# BBBExtend.net
KiCad netlist of a schematic drawn in Altium Designer
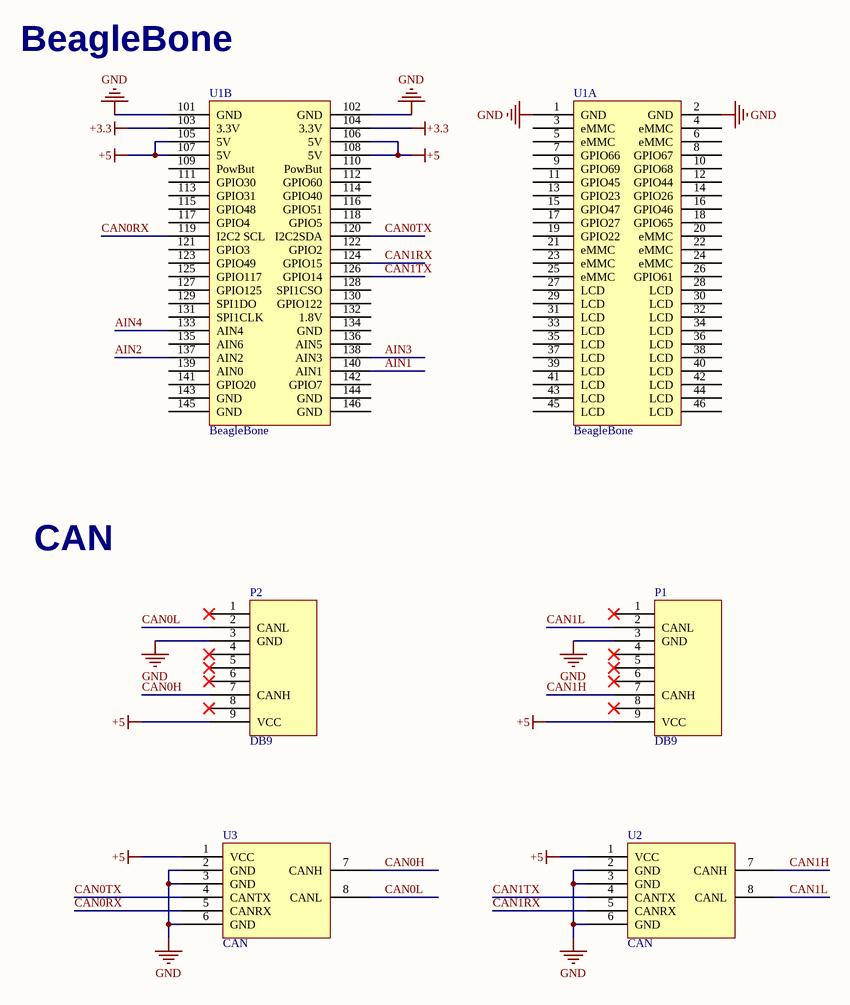
[diagram p0: BBBExtend.SchDoc]

(export (version "E")
  (design (tool "Eeschema 10.0.6"))
  (components
    (comp (ref "P1") (value "DB9") (footprint "DB9") (libsource (lib "Schlib1") (part "DB9")))
    (comp (ref "P2") (value "DB9") (footprint "DB9") (libsource (lib "Schlib1") (part "DB9")))
    (comp (ref "U1")
      (value "BeagleBone")
      (footprint "BeagleBoneB")
      (libsource (lib "Schlib1") (part "BeagleBone"))
    )
    (comp (ref "U2") (value "CAN") (footprint "CANTRer") (libsource (lib "Schlib1") (part "CAN")))
    (comp (ref "U3") (value "CAN") (footprint "CANTRer") (libsource (lib "Schlib1") (part "CAN")))
  )
  (nets
    (net (code "1") (name "+3.3") (class "Default")
      (node (ref "U1") (pin "103") (pinfunction "3.3V_103") (pintype "passive"))
      (node (ref "U1") (pin "104") (pinfunction "3.3V_104") (pintype "passive"))
    )
    (net (code "2") (name "+5") (class "Default")
      (node (ref "P1") (pin "9") (pinfunction "VCC_9") (pintype "passive"))
      (node (ref "P2") (pin "9") (pinfunction "VCC_9") (pintype "passive"))
      (node (ref "U1") (pin "105") (pinfunction "5V_105") (pintype "passive"))
      (node (ref "U1") (pin "106") (pinfunction "5V_106") (pintype "passive"))
      (node (ref "U1") (pin "107") (pinfunction "5V_107") (pintype "passive"))
      (node (ref "U1") (pin "108") (pinfunction "5V_108") (pintype "passive"))
      (node (ref "U2") (pin "1") (pinfunction "VCC_1") (pintype "passive"))
      (node (ref "U3") (pin "1") (pinfunction "VCC_1") (pintype "passive"))
    )
    (net (code "3") (name "/AIN1") (class "Default")
      (node (ref "U1") (pin "140") (pinfunction "AIN1_140") (pintype "passive"))
    )
    (net (code "4") (name "/AIN2") (class "Default")
      (node (ref "U1") (pin "137") (pinfunction "AIN2_137") (pintype "passive"))
    )
    (net (code "5") (name "/AIN3") (class "Default")
      (node (ref "U1") (pin "138") (pinfunction "AIN3_138") (pintype "passive"))
    )
    (net (code "6") (name "/AIN4") (class "Default")
      (node (ref "U1") (pin "133") (pinfunction "AIN4_133") (pintype "passive"))
    )
    (net (code "7") (name "/CAN0H") (class "Default")
      (node (ref "P2") (pin "7") (pinfunction "CANH_7") (pintype "passive"))
      (node (ref "U3") (pin "7") (pinfunction "CANH_7") (pintype "passive"))
    )
    (net (code "8") (name "/CAN0L") (class "Default")
      (node (ref "P2") (pin "2") (pinfunction "CANL_2") (pintype "passive"))
      (node (ref "U3") (pin "8") (pinfunction "CANL_8") (pintype "passive"))
    )
    (net (code "9") (name "/CAN0RX") (class "Default")
      (node (ref "U1") (pin "119") (pinfunction "I2C2_SCL_119") (pintype "passive"))
      (node (ref "U3") (pin "5") (pinfunction "CANRX_5") (pintype "passive"))
    )
    (net (code "10") (name "/CAN0TX") (class "Default")
      (node (ref "U1") (pin "120") (pinfunction "I2C2SDA_120") (pintype "passive"))
      (node (ref "U3") (pin "4") (pinfunction "CANTX_4") (pintype "passive"))
    )
    (net (code "11") (name "/CAN1H") (class "Default")
      (node (ref "P1") (pin "7") (pinfunction "CANH_7") (pintype "passive"))
      (node (ref "U2") (pin "7") (pinfunction "CANH_7") (pintype "passive"))
    )
    (net (code "12") (name "/CAN1L") (class "Default")
      (node (ref "P1") (pin "2") (pinfunction "CANL_2") (pintype "passive"))
      (node (ref "U2") (pin "8") (pinfunction "CANL_8") (pintype "passive"))
    )
    (net (code "13") (name "/CAN1RX") (class "Default")
      (node (ref "U1") (pin "124") (pinfunction "GPIO15_124") (pintype "passive"))
      (node (ref "U2") (pin "5") (pinfunction "CANRX_5") (pintype "passive"))
    )
    (net (code "14") (name "/CAN1TX") (class "Default")
      (node (ref "U1") (pin "126") (pinfunction "GPIO14_126") (pintype "passive"))
      (node (ref "U2") (pin "4") (pinfunction "CANTX_4") (pintype "passive"))
    )
    (net (code "15") (name "GND") (class "Default")
      (node (ref "P1") (pin "3") (pinfunction "GND_3") (pintype "passive"))
      (node (ref "P2") (pin "3") (pinfunction "GND_3") (pintype "passive"))
      (node (ref "U1") (pin "1") (pinfunction "GND_1") (pintype "passive"))
      (node (ref "U1") (pin "101") (pinfunction "GND_101") (pintype "passive"))
      (node (ref "U1") (pin "102") (pinfunction "GND_102") (pintype "passive"))
      (node (ref "U1") (pin "2") (pinfunction "GND_2") (pintype "passive"))
      (node (ref "U2") (pin "2") (pinfunction "GND_2") (pintype "passive"))
      (node (ref "U2") (pin "3") (pinfunction "GND_3") (pintype "passive"))
      (node (ref "U2") (pin "6") (pinfunction "GND_6") (pintype "passive"))
      (node (ref "U3") (pin "2") (pinfunction "GND_2") (pintype "passive"))
      (node (ref "U3") (pin "3") (pinfunction "GND_3") (pintype "passive"))
      (node (ref "U3") (pin "6") (pinfunction "GND_6") (pintype "passive"))
    )
    (net (code "16") (name "unconnected-(P1-Pad1)") (class "Default")
      (node (ref "P1") (pin "1") (pintype "passive+no_connect"))
    )
    (net (code "17") (name "unconnected-(P1-Pad4)") (class "Default")
      (node (ref "P1") (pin "4") (pintype "passive+no_connect"))
    )
    (net (code "18") (name "unconnected-(P1-Pad5)") (class "Default")
      (node (ref "P1") (pin "5") (pintype "passive+no_connect"))
    )
    (net (code "19") (name "unconnected-(P1-Pad6)") (class "Default")
      (node (ref "P1") (pin "6") (pintype "passive+no_connect"))
    )
    (net (code "20") (name "unconnected-(P1-Pad8)") (class "Default")
      (node (ref "P1") (pin "8") (pintype "passive+no_connect"))
    )
    (net (code "21") (name "unconnected-(P2-Pad1)") (class "Default")
      (node (ref "P2") (pin "1") (pintype "passive+no_connect"))
    )
    (net (code "22") (name "unconnected-(P2-Pad4)") (class "Default")
      (node (ref "P2") (pin "4") (pintype "passive+no_connect"))
    )
    (net (code "23") (name "unconnected-(P2-Pad5)") (class "Default")
      (node (ref "P2") (pin "5") (pintype "passive+no_connect"))
    )
    (net (code "24") (name "unconnected-(P2-Pad6)") (class "Default")
      (node (ref "P2") (pin "6") (pintype "passive+no_connect"))
    )
    (net (code "25") (name "unconnected-(P2-Pad8)") (class "Default")
      (node (ref "P2") (pin "8") (pintype "passive+no_connect"))
    )
    (net (code "26") (name "unconnected-(U1A-GPIO22-Pad19)") (class "Default")
      (node (ref "U1") (pin "19") (pinfunction "GPIO22_19") (pintype "passive"))
    )
    (net (code "27") (name "unconnected-(U1A-GPIO23-Pad13)") (class "Default")
      (node (ref "U1") (pin "13") (pinfunction "GPIO23_13") (pintype "passive"))
    )
    (net (code "28") (name "unconnected-(U1A-GPIO26-Pad14)") (class "Default")
      (node (ref "U1") (pin "14") (pinfunction "GPIO26_14") (pintype "passive"))
    )
    (net (code "29") (name "unconnected-(U1A-GPIO27-Pad17)") (class "Default")
      (node (ref "U1") (pin "17") (pinfunction "GPIO27_17") (pintype "passive"))
    )
    (net (code "30") (name "unconnected-(U1A-GPIO44-Pad12)") (class "Default")
      (node (ref "U1") (pin "12") (pinfunction "GPIO44_12") (pintype "passive"))
    )
    (net (code "31") (name "unconnected-(U1A-GPIO45-Pad11)") (class "Default")
      (node (ref "U1") (pin "11") (pinfunction "GPIO45_11") (pintype "passive"))
    )
    (net (code "32") (name "unconnected-(U1A-GPIO46-Pad16)") (class "Default")
      (node (ref "U1") (pin "16") (pinfunction "GPIO46_16") (pintype "passive"))
    )
    (net (code "33") (name "unconnected-(U1A-GPIO47-Pad15)") (class "Default")
      (node (ref "U1") (pin "15") (pinfunction "GPIO47_15") (pintype "passive"))
    )
    (net (code "34") (name "unconnected-(U1A-GPIO61-Pad26)") (class "Default")
      (node (ref "U1") (pin "26") (pinfunction "GPIO61_26") (pintype "passive"))
    )
    (net (code "35") (name "unconnected-(U1A-GPIO65-Pad18)") (class "Default")
      (node (ref "U1") (pin "18") (pinfunction "GPIO65_18") (pintype "passive"))
    )
    (net (code "36") (name "unconnected-(U1A-GPIO66-Pad7)") (class "Default")
      (node (ref "U1") (pin "7") (pinfunction "GPIO66_7") (pintype "passive"))
    )
    (net (code "37") (name "unconnected-(U1A-GPIO67-Pad8)") (class "Default")
      (node (ref "U1") (pin "8") (pinfunction "GPIO67_8") (pintype "passive"))
    )
    (net (code "38") (name "unconnected-(U1A-GPIO68-Pad10)") (class "Default")
      (node (ref "U1") (pin "10") (pinfunction "GPIO68_10") (pintype "passive"))
    )
    (net (code "39") (name "unconnected-(U1A-GPIO69-Pad9)") (class "Default")
      (node (ref "U1") (pin "9") (pinfunction "GPIO69_9") (pintype "passive"))
    )
    (net (code "40") (name "unconnected-(U1A-LCD-Pad27)") (class "Default")
      (node (ref "U1") (pin "27") (pinfunction "LCD_27") (pintype "passive"))
    )
    (net (code "41") (name "unconnected-(U1A-LCD-Pad28)") (class "Default")
      (node (ref "U1") (pin "28") (pinfunction "LCD_28") (pintype "passive"))
    )
    (net (code "42") (name "unconnected-(U1A-LCD-Pad29)") (class "Default")
      (node (ref "U1") (pin "29") (pinfunction "LCD_29") (pintype "passive"))
    )
    (net (code "43") (name "unconnected-(U1A-LCD-Pad30)") (class "Default")
      (node (ref "U1") (pin "30") (pinfunction "LCD_30") (pintype "passive"))
    )
    (net (code "44") (name "unconnected-(U1A-LCD-Pad31)") (class "Default")
      (node (ref "U1") (pin "31") (pinfunction "LCD_31") (pintype "passive"))
    )
    (net (code "45") (name "unconnected-(U1A-LCD-Pad32)") (class "Default")
      (node (ref "U1") (pin "32") (pinfunction "LCD_32") (pintype "passive"))
    )
    (net (code "46") (name "unconnected-(U1A-LCD-Pad33)") (class "Default")
      (node (ref "U1") (pin "33") (pinfunction "LCD_33") (pintype "passive"))
    )
    (net (code "47") (name "unconnected-(U1A-LCD-Pad34)") (class "Default")
      (node (ref "U1") (pin "34") (pinfunction "LCD_34") (pintype "passive"))
    )
    (net (code "48") (name "unconnected-(U1A-LCD-Pad35)") (class "Default")
      (node (ref "U1") (pin "35") (pinfunction "LCD_35") (pintype "passive"))
    )
    (net (code "49") (name "unconnected-(U1A-LCD-Pad36)") (class "Default")
      (node (ref "U1") (pin "36") (pinfunction "LCD_36") (pintype "passive"))
    )
    (net (code "50") (name "unconnected-(U1A-LCD-Pad37)") (class "Default")
      (node (ref "U1") (pin "37") (pinfunction "LCD_37") (pintype "passive"))
    )
    (net (code "51") (name "unconnected-(U1A-LCD-Pad38)") (class "Default")
      (node (ref "U1") (pin "38") (pinfunction "LCD_38") (pintype "passive"))
    )
    (net (code "52") (name "unconnected-(U1A-LCD-Pad39)") (class "Default")
      (node (ref "U1") (pin "39") (pinfunction "LCD_39") (pintype "passive"))
    )
    (net (code "53") (name "unconnected-(U1A-LCD-Pad40)") (class "Default")
      (node (ref "U1") (pin "40") (pinfunction "LCD_40") (pintype "passive"))
    )
    (net (code "54") (name "unconnected-(U1A-LCD-Pad41)") (class "Default")
      (node (ref "U1") (pin "41") (pinfunction "LCD_41") (pintype "passive"))
    )
    (net (code "55") (name "unconnected-(U1A-LCD-Pad42)") (class "Default")
      (node (ref "U1") (pin "42") (pinfunction "LCD_42") (pintype "passive"))
    )
    (net (code "56") (name "unconnected-(U1A-LCD-Pad43)") (class "Default")
      (node (ref "U1") (pin "43") (pinfunction "LCD_43") (pintype "passive"))
    )
    (net (code "57") (name "unconnected-(U1A-LCD-Pad44)") (class "Default")
      (node (ref "U1") (pin "44") (pinfunction "LCD_44") (pintype "passive"))
    )
    (net (code "58") (name "unconnected-(U1A-LCD-Pad45)") (class "Default")
      (node (ref "U1") (pin "45") (pinfunction "LCD_45") (pintype "passive"))
    )
    (net (code "59") (name "unconnected-(U1A-LCD-Pad46)") (class "Default")
      (node (ref "U1") (pin "46") (pinfunction "LCD_46") (pintype "passive"))
    )
    (net (code "60") (name "unconnected-(U1A-eMMC-Pad3)") (class "Default")
      (node (ref "U1") (pin "3") (pinfunction "eMMC_3") (pintype "passive"))
    )
    (net (code "61") (name "unconnected-(U1A-eMMC-Pad4)") (class "Default")
      (node (ref "U1") (pin "4") (pinfunction "eMMC_4") (pintype "passive"))
    )
    (net (code "62") (name "unconnected-(U1A-eMMC-Pad5)") (class "Default")
      (node (ref "U1") (pin "5") (pinfunction "eMMC_5") (pintype "passive"))
    )
    (net (code "63") (name "unconnected-(U1A-eMMC-Pad6)") (class "Default")
      (node (ref "U1") (pin "6") (pinfunction "eMMC_6") (pintype "passive"))
    )
    (net (code "64") (name "unconnected-(U1A-eMMC-Pad20)") (class "Default")
      (node (ref "U1") (pin "20") (pinfunction "eMMC_20") (pintype "passive"))
    )
    (net (code "65") (name "unconnected-(U1A-eMMC-Pad21)") (class "Default")
      (node (ref "U1") (pin "21") (pinfunction "eMMC_21") (pintype "passive"))
    )
    (net (code "66") (name "unconnected-(U1A-eMMC-Pad22)") (class "Default")
      (node (ref "U1") (pin "22") (pinfunction "eMMC_22") (pintype "passive"))
    )
    (net (code "67") (name "unconnected-(U1A-eMMC-Pad23)") (class "Default")
      (node (ref "U1") (pin "23") (pinfunction "eMMC_23") (pintype "passive"))
    )
    (net (code "68") (name "unconnected-(U1A-eMMC-Pad24)") (class "Default")
      (node (ref "U1") (pin "24") (pinfunction "eMMC_24") (pintype "passive"))
    )
    (net (code "69") (name "unconnected-(U1A-eMMC-Pad25)") (class "Default")
      (node (ref "U1") (pin "25") (pinfunction "eMMC_25") (pintype "passive"))
    )
    (net (code "70") (name "unconnected-(U1B-1.8V-Pad132)") (class "Default")
      (node (ref "U1") (pin "132") (pinfunction "1.8V_132") (pintype "passive"))
    )
    (net (code "71") (name "unconnected-(U1B-AIN0-Pad139)") (class "Default")
      (node (ref "U1") (pin "139") (pinfunction "AIN0_139") (pintype "passive"))
    )
    (net (code "72") (name "unconnected-(U1B-AIN5-Pad136)") (class "Default")
      (node (ref "U1") (pin "136") (pinfunction "AIN5_136") (pintype "passive"))
    )
    (net (code "73") (name "unconnected-(U1B-AIN6-Pad135)") (class "Default")
      (node (ref "U1") (pin "135") (pinfunction "AIN6_135") (pintype "passive"))
    )
    (net (code "74") (name "unconnected-(U1B-GND-Pad134)") (class "Default")
      (node (ref "U1") (pin "134") (pinfunction "GND_134") (pintype "passive"))
    )
    (net (code "75") (name "unconnected-(U1B-GND-Pad143)") (class "Default")
      (node (ref "U1") (pin "143") (pinfunction "GND_143") (pintype "passive"))
    )
    (net (code "76") (name "unconnected-(U1B-GND-Pad144)") (class "Default")
      (node (ref "U1") (pin "144") (pinfunction "GND_144") (pintype "passive"))
    )
    (net (code "77") (name "unconnected-(U1B-GND-Pad145)") (class "Default")
      (node (ref "U1") (pin "145") (pinfunction "GND_145") (pintype "passive"))
    )
    (net (code "78") (name "unconnected-(U1B-GND-Pad146)") (class "Default")
      (node (ref "U1") (pin "146") (pinfunction "GND_146") (pintype "passive"))
    )
    (net (code "79") (name "unconnected-(U1B-GPIO2-Pad122)") (class "Default")
      (node (ref "U1") (pin "122") (pinfunction "GPIO2_122") (pintype "passive"))
    )
    (net (code "80") (name "unconnected-(U1B-GPIO3-Pad121)") (class "Default")
      (node (ref "U1") (pin "121") (pinfunction "GPIO3_121") (pintype "passive"))
    )
    (net (code "81") (name "unconnected-(U1B-GPIO4-Pad117)") (class "Default")
      (node (ref "U1") (pin "117") (pinfunction "GPIO4_117") (pintype "passive"))
    )
    (net (code "82") (name "unconnected-(U1B-GPIO5-Pad118)") (class "Default")
      (node (ref "U1") (pin "118") (pinfunction "GPIO5_118") (pintype "passive"))
    )
    (net (code "83") (name "unconnected-(U1B-GPIO7-Pad142)") (class "Default")
      (node (ref "U1") (pin "142") (pinfunction "GPIO7_142") (pintype "passive"))
    )
    (net (code "84") (name "unconnected-(U1B-GPIO20-Pad141)") (class "Default")
      (node (ref "U1") (pin "141") (pinfunction "GPIO20_141") (pintype "passive"))
    )
    (net (code "85") (name "unconnected-(U1B-GPIO30-Pad111)") (class "Default")
      (node (ref "U1") (pin "111") (pinfunction "GPIO30_111") (pintype "passive"))
    )
    (net (code "86") (name "unconnected-(U1B-GPIO31-Pad113)") (class "Default")
      (node (ref "U1") (pin "113") (pinfunction "GPIO31_113") (pintype "passive"))
    )
    (net (code "87") (name "unconnected-(U1B-GPIO40-Pad114)") (class "Default")
      (node (ref "U1") (pin "114") (pinfunction "GPIO40_114") (pintype "passive"))
    )
    (net (code "88") (name "unconnected-(U1B-GPIO48-Pad115)") (class "Default")
      (node (ref "U1") (pin "115") (pinfunction "GPIO48_115") (pintype "passive"))
    )
    (net (code "89") (name "unconnected-(U1B-GPIO49-Pad123)") (class "Default")
      (node (ref "U1") (pin "123") (pinfunction "GPIO49_123") (pintype "passive"))
    )
    (net (code "90") (name "unconnected-(U1B-GPIO51-Pad116)") (class "Default")
      (node (ref "U1") (pin "116") (pinfunction "GPIO51_116") (pintype "passive"))
    )
    (net (code "91") (name "unconnected-(U1B-GPIO60-Pad112)") (class "Default")
      (node (ref "U1") (pin "112") (pinfunction "GPIO60_112") (pintype "passive"))
    )
    (net (code "92") (name "unconnected-(U1B-GPIO117-Pad125)") (class "Default")
      (node (ref "U1") (pin "125") (pinfunction "GPIO117_125") (pintype "passive"))
    )
    (net (code "93") (name "unconnected-(U1B-GPIO122-Pad130)") (class "Default")
      (node (ref "U1") (pin "130") (pinfunction "GPIO122_130") (pintype "passive"))
    )
    (net (code "94") (name "unconnected-(U1B-GPIO125-Pad127)") (class "Default")
      (node (ref "U1") (pin "127") (pinfunction "GPIO125_127") (pintype "passive"))
    )
    (net (code "95") (name "unconnected-(U1B-PowBut-Pad109)") (class "Default")
      (node (ref "U1") (pin "109") (pinfunction "PowBut_109") (pintype "passive"))
    )
    (net (code "96") (name "unconnected-(U1B-PowBut-Pad110)") (class "Default")
      (node (ref "U1") (pin "110") (pinfunction "PowBut_110") (pintype "passive"))
    )
    (net (code "97") (name "unconnected-(U1B-SPI1CLK-Pad131)") (class "Default")
      (node (ref "U1") (pin "131") (pinfunction "SPI1CLK_131") (pintype "passive"))
    )
    (net (code "98") (name "unconnected-(U1B-SPI1CSO-Pad128)") (class "Default")
      (node (ref "U1") (pin "128") (pinfunction "SPI1CSO_128") (pintype "passive"))
    )
    (net (code "99") (name "unconnected-(U1B-SPI1DO-Pad129)") (class "Default")
      (node (ref "U1") (pin "129") (pinfunction "SPI1DO_129") (pintype "passive"))
    )
  )
)
